# dron_shm.net
KiCad netlist of a schematic drawn in EasyEDA
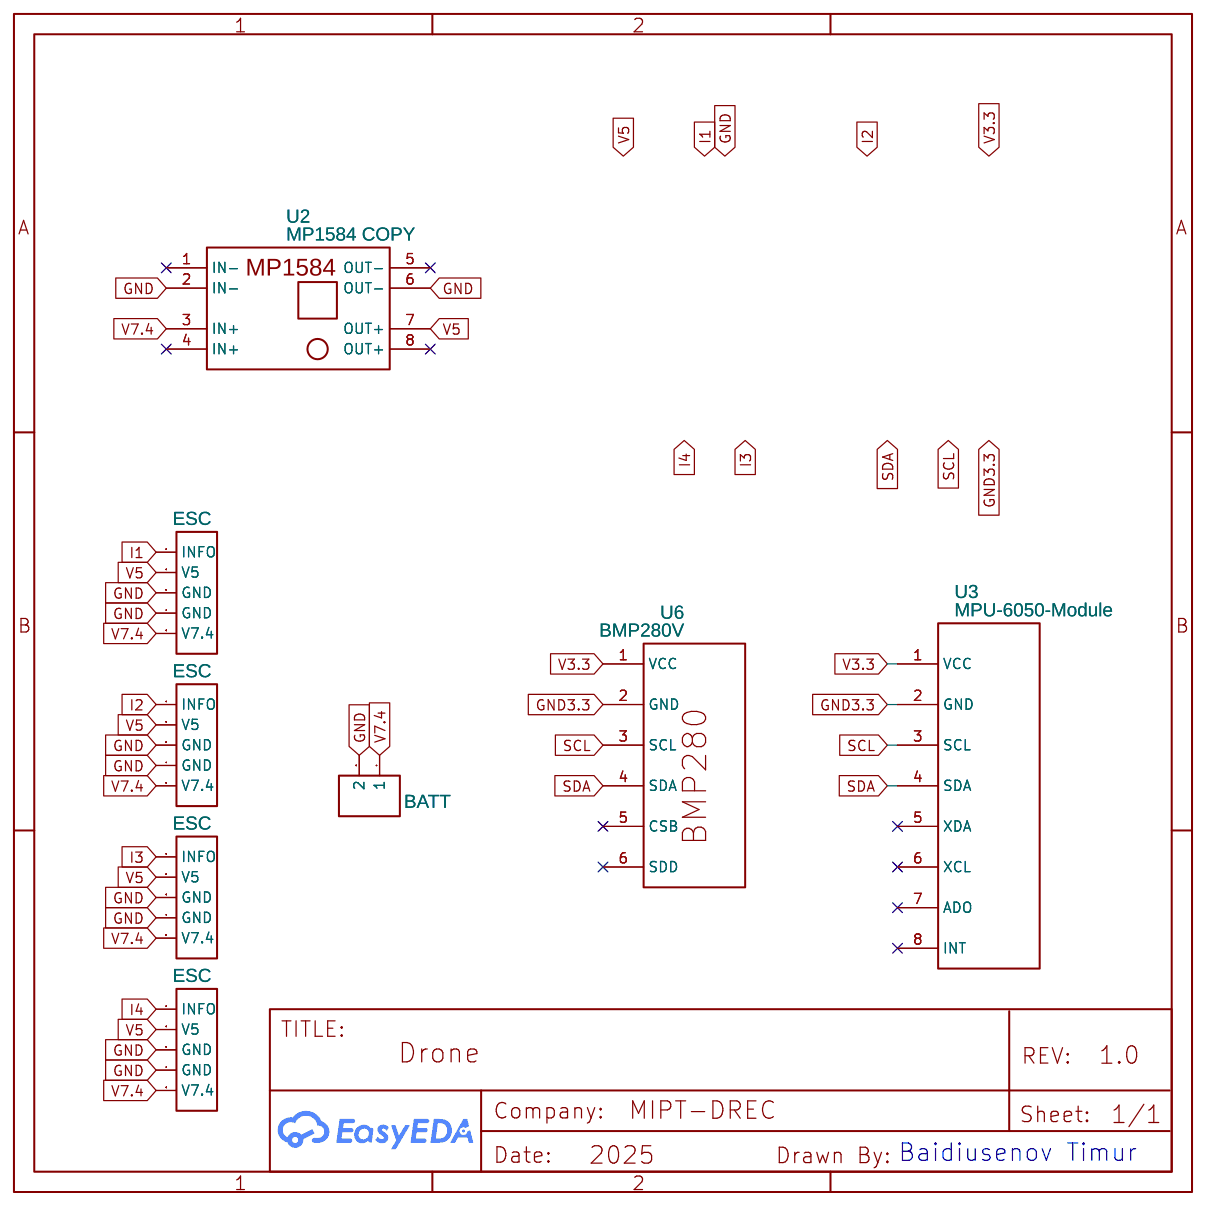
[diagram p0: schematic sheet]

(export (version "E")
  (design (tool "Eeschema 10.0.6"))
  (components
    (comp (ref "ECS1") (value "ESC") (libsource (lib "") (part "HDR-F-2.54_1x5")))
    (comp (ref "ECS2") (value "ESC") (libsource (lib "") (part "HDR-F-2.54_1x5")))
    (comp (ref "ECS3") (value "ESC") (libsource (lib "") (part "HDR-F-2.54_1x5")))
    (comp (ref "ECS4") (value "ESC") (libsource (lib "") (part "HDR-F-2.54_1x5")))
    (comp (ref "H1") (value "BATT") (libsource (lib "") (part "HDR-F-2.54_1x2")))
    (comp (ref "U2")
      (value "MP1584 COPY")
      (fields (field (name "Manufacturer Part") "MP1584EN"))
      (libsource (lib "") (part "MP1584 COPY"))
    )
    (comp (ref "U3") (value "MPU-6050-Module") (libsource (lib "") (part "MPU-6050-Module")))
    (comp (ref "U6") (value "BMP280V") (libsource (lib "") (part "BMP280V")))
  )
  (nets
    (net (code "1") (name "GND") (class "Default")
      (node (ref "ECS1") (pin "3") (pinfunction "GND_3") (pintype "unspecified"))
      (node (ref "ECS1") (pin "4") (pinfunction "GND_4") (pintype "unspecified"))
      (node (ref "ECS2") (pin "3") (pinfunction "GND_3") (pintype "unspecified"))
      (node (ref "ECS2") (pin "4") (pinfunction "GND_4") (pintype "unspecified"))
      (node (ref "ECS3") (pin "3") (pinfunction "GND_3") (pintype "unspecified"))
      (node (ref "ECS3") (pin "4") (pinfunction "GND_4") (pintype "unspecified"))
      (node (ref "ECS4") (pin "3") (pinfunction "GND_3") (pintype "unspecified"))
      (node (ref "ECS4") (pin "4") (pinfunction "GND_4") (pintype "unspecified"))
      (node (ref "H1") (pin "2") (pinfunction "2_2") (pintype "input"))
      (node (ref "U2") (pin "2") (pinfunction "IN-_2") (pintype "unspecified"))
      (node (ref "U2") (pin "6") (pinfunction "OUT-_6") (pintype "unspecified"))
    )
    (net (code "2") (name "GND3.3") (class "Default")
      (node (ref "U3") (pin "2") (pinfunction "GND_2") (pintype "unspecified"))
      (node (ref "U6") (pin "2") (pinfunction "GND_2") (pintype "unspecified"))
    )
    (net (code "3") (name "I1") (class "Default")
      (node (ref "ECS4") (pin "1") (pinfunction "INFO_1") (pintype "unspecified"))
    )
    (net (code "4") (name "I2") (class "Default")
      (node (ref "ECS1") (pin "1") (pinfunction "INFO_1") (pintype "unspecified"))
    )
    (net (code "5") (name "I3") (class "Default")
      (node (ref "ECS2") (pin "1") (pinfunction "INFO_1") (pintype "unspecified"))
    )
    (net (code "6") (name "I4") (class "Default")
      (node (ref "ECS3") (pin "1") (pinfunction "INFO_1") (pintype "unspecified"))
    )
    (net (code "7") (name "SCL") (class "Default")
      (node (ref "U3") (pin "3") (pinfunction "SCL_3") (pintype "unspecified"))
      (node (ref "U6") (pin "3") (pinfunction "SCL_3") (pintype "unspecified"))
    )
    (net (code "8") (name "SDA") (class "Default")
      (node (ref "U3") (pin "4") (pinfunction "SDA_4") (pintype "unspecified"))
      (node (ref "U6") (pin "4") (pinfunction "SDA_4") (pintype "unspecified"))
    )
    (net (code "9") (name "V3.3") (class "Default")
      (node (ref "U3") (pin "1") (pinfunction "VCC_1") (pintype "unspecified"))
      (node (ref "U6") (pin "1") (pinfunction "VCC_1") (pintype "unspecified"))
    )
    (net (code "10") (name "V5") (class "Default")
      (node (ref "ECS1") (pin "2") (pinfunction "V5_2") (pintype "unspecified"))
      (node (ref "ECS2") (pin "2") (pinfunction "V5_2") (pintype "unspecified"))
      (node (ref "ECS3") (pin "2") (pinfunction "V5_2") (pintype "unspecified"))
      (node (ref "ECS4") (pin "2") (pinfunction "V5_2") (pintype "unspecified"))
      (node (ref "U2") (pin "7") (pinfunction "OUT+_7") (pintype "unspecified"))
    )
    (net (code "11") (name "V7.4") (class "Default")
      (node (ref "ECS1") (pin "5") (pinfunction "V7.4_5") (pintype "unspecified"))
      (node (ref "ECS2") (pin "5") (pinfunction "V7.4_5") (pintype "unspecified"))
      (node (ref "ECS3") (pin "5") (pinfunction "V7.4_5") (pintype "unspecified"))
      (node (ref "ECS4") (pin "5") (pinfunction "V7.4_5") (pintype "unspecified"))
      (node (ref "H1") (pin "1") (pinfunction "1_1") (pintype "input"))
      (node (ref "U2") (pin "3") (pinfunction "IN+_3") (pintype "unspecified"))
    )
    (net (code "12") (name "unconnected-(U2-IN+-Pad4)") (class "Default")
      (node (ref "U2") (pin "4") (pinfunction "IN+_4") (pintype "unspecified+no_connect"))
    )
    (net (code "13") (name "unconnected-(U2-IN--Pad1)") (class "Default")
      (node (ref "U2") (pin "1") (pinfunction "IN-_1") (pintype "unspecified+no_connect"))
    )
    (net (code "14") (name "unconnected-(U2-OUT+-Pad8)") (class "Default")
      (node (ref "U2") (pin "8") (pinfunction "OUT+_8") (pintype "unspecified+no_connect"))
    )
    (net (code "15") (name "unconnected-(U2-OUT--Pad5)") (class "Default")
      (node (ref "U2") (pin "5") (pinfunction "OUT-_5") (pintype "unspecified+no_connect"))
    )
    (net (code "16") (name "unconnected-(U3-ADO-Pad7)") (class "Default")
      (node (ref "U3") (pin "7") (pinfunction "ADO_7") (pintype "unspecified+no_connect"))
    )
    (net (code "17") (name "unconnected-(U3-INT-Pad8)") (class "Default")
      (node (ref "U3") (pin "8") (pinfunction "INT_8") (pintype "unspecified+no_connect"))
    )
    (net (code "18") (name "unconnected-(U3-XCL-Pad6)") (class "Default")
      (node (ref "U3") (pin "6") (pinfunction "XCL_6") (pintype "unspecified+no_connect"))
    )
    (net (code "19") (name "unconnected-(U3-XDA-Pad5)") (class "Default")
      (node (ref "U3") (pin "5") (pinfunction "XDA_5") (pintype "unspecified+no_connect"))
    )
    (net (code "20") (name "unconnected-(U6-CSB-Pad5)") (class "Default")
      (node (ref "U6") (pin "5") (pinfunction "CSB_5") (pintype "unspecified+no_connect"))
    )
    (net (code "21") (name "unconnected-(U6-SDD-Pad6)") (class "Default")
      (node (ref "U6") (pin "6") (pinfunction "SDD_6") (pintype "unspecified+no_connect"))
    )
  )
)
